# CATS-FAT-Mageto.net
KiCad netlist of a schematic drawn in Altium Designer
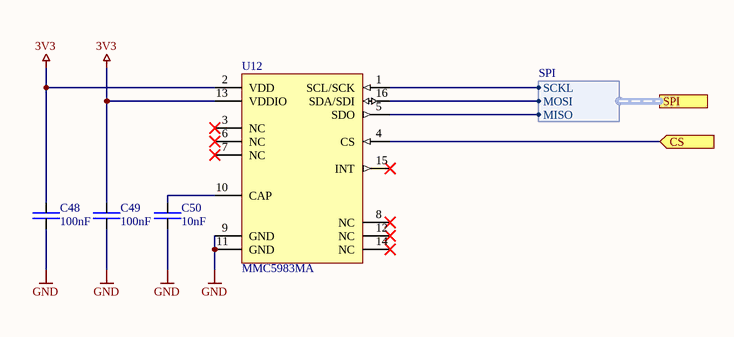
[diagram p0: CATS-FAT-Mageto.SchDoc]

(export (version "E")
  (design (tool "Eeschema 10.0.6"))
  (components
    (comp (ref "C48")
      (value "100nF")
      (footprint "SMD Keramikkondensator 0603")
      (description "SMD Ceramic Capacitor E6")
      (libsource (lib "Ceramic Capacitors-E6") (part "E6 - 100nF"))
    )
    (comp (ref "C49")
      (value "100nF")
      (footprint "SMD Keramikkondensator 0603")
      (description "SMD Ceramic Capacitor E6")
      (libsource (lib "Ceramic Capacitors-E6") (part "E6 - 100nF"))
    )
    (comp (ref "C50")
      (value "10nF")
      (footprint "SMD Keramikkondensator 0603")
      (description "SMD Ceramic Capacitor E6")
      (libsource (lib "Ceramic Capacitors-E6") (part "E6 - 10nF"))
    )
    (comp (ref "U12")
      (value "MMC5983MA")
      (footprint "SMD IC LGA-16 4/4")
      (description "High Performance\r\n3-axis Magnetic Sensor")
      (libsource (lib "Sensors") (part "MMC5983MA"))
    )
  )
  (nets
    (net (code "2") (name "/CS") (class "Default")
      (node (ref "U12") (pin "4") (pinfunction "CS_4") (pintype "input"))
    )
    (net (code "3") (name "/MISO") (class "Default")
      (node (ref "U12") (pin "5") (pinfunction "SDO_5") (pintype "output"))
    )
    (net (code "4") (name "/MOSI") (class "Default")
      (node (ref "U12") (pin "16") (pinfunction "SDA/SDI_16") (pintype "bidirectional"))
    )
    (net (code "5") (name "/SCKL") (class "Default")
      (node (ref "U12") (pin "1") (pinfunction "SCL/SCK_1") (pintype "input"))
    )
    (net (code "7") (name "3V3") (class "Default")
      (node (ref "C48") (pin "2") (pinfunction "2_2") (pintype "passive"))
      (node (ref "C49") (pin "2") (pinfunction "2_2") (pintype "passive"))
      (node (ref "U12") (pin "13") (pinfunction "VDDIO_13") (pintype "passive"))
      (node (ref "U12") (pin "2") (pinfunction "VDD_2") (pintype "passive"))
    )
    (net (code "8") (name "GND") (class "Default")
      (node (ref "C48") (pin "1") (pinfunction "1_1") (pintype "passive"))
      (node (ref "C49") (pin "1") (pinfunction "1_1") (pintype "passive"))
      (node (ref "C50") (pin "1") (pinfunction "1_1") (pintype "passive"))
      (node (ref "U12") (pin "11") (pinfunction "GND_11") (pintype "passive"))
      (node (ref "U12") (pin "9") (pinfunction "GND_9") (pintype "passive"))
    )
    (net (code "9") (name "Net-(U12-CAP)") (class "Default")
      (node (ref "C50") (pin "2") (pinfunction "2_2") (pintype "passive"))
      (node (ref "U12") (pin "10") (pinfunction "CAP_10") (pintype "passive"))
    )
    (net (code "10") (name "unconnected-(U12-INT-Pad15)") (class "Default")
      (node (ref "U12") (pin "15") (pinfunction "INT_15") (pintype "output+no_connect"))
    )
    (net (code "11") (name "unconnected-(U12-NC-Pad3)") (class "Default")
      (node (ref "U12") (pin "3") (pinfunction "NC_3") (pintype "passive+no_connect"))
    )
    (net (code "12") (name "unconnected-(U12-NC-Pad6)") (class "Default")
      (node (ref "U12") (pin "6") (pinfunction "NC_6") (pintype "passive+no_connect"))
    )
    (net (code "13") (name "unconnected-(U12-NC-Pad7)") (class "Default")
      (node (ref "U12") (pin "7") (pinfunction "NC_7") (pintype "passive+no_connect"))
    )
    (net (code "14") (name "unconnected-(U12-NC-Pad8)") (class "Default")
      (node (ref "U12") (pin "8") (pinfunction "NC_8") (pintype "passive+no_connect"))
    )
    (net (code "15") (name "unconnected-(U12-NC-Pad12)") (class "Default")
      (node (ref "U12") (pin "12") (pinfunction "NC_12") (pintype "passive+no_connect"))
    )
    (net (code "16") (name "unconnected-(U12-NC-Pad14)") (class "Default")
      (node (ref "U12") (pin "14") (pinfunction "NC_14") (pintype "passive+no_connect"))
    )
  )
)
